# GPSClockISA.net
KiCad netlist of a schematic drawn in EAGLE
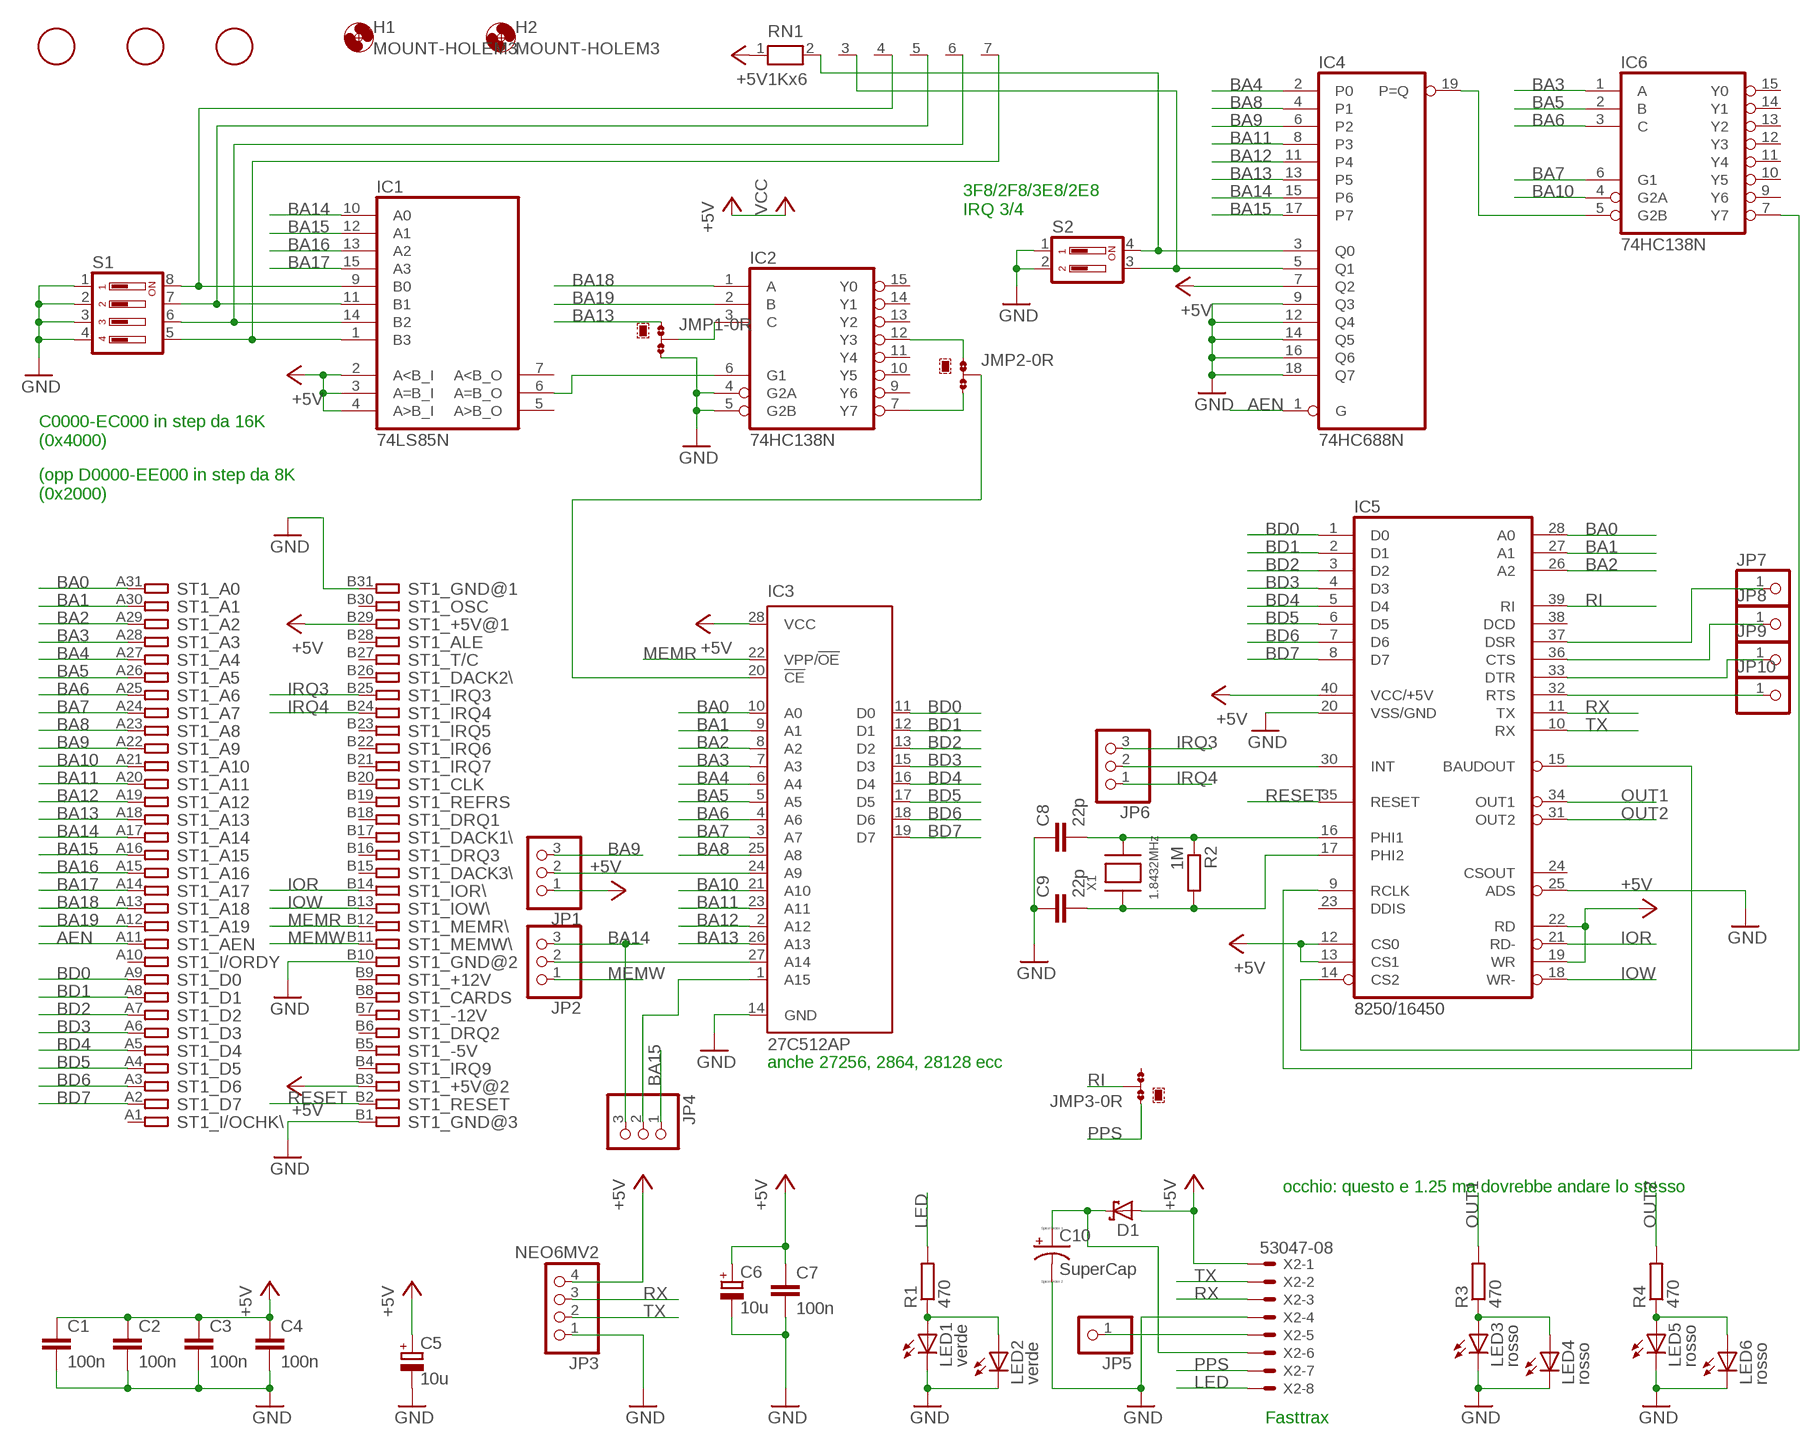
[diagram p0: schematic, sheet 1]

(export (version "E")
  (design (tool "Eeschema 10.0.6"))
  (components
    (comp (ref "C1")
      (value "100n")
      (footprint "eagle-import:C0805")
      (libsource (lib "eagle-import") (part "C-EUC0805"))
    )
    (comp (ref "C2")
      (value "100n")
      (footprint "eagle-import:C0805")
      (libsource (lib "eagle-import") (part "C-EUC0805"))
    )
    (comp (ref "C3")
      (value "100n")
      (footprint "eagle-import:C0805")
      (libsource (lib "eagle-import") (part "C-EUC0805"))
    )
    (comp (ref "C4")
      (value "100n")
      (footprint "eagle-import:C0805")
      (libsource (lib "eagle-import") (part "C-EUC0805"))
    )
    (comp (ref "C5")
      (value "10u")
      (footprint "eagle-import:SMC_D")
      (libsource (lib "eagle-import") (part "CPOL-EUSMCD"))
    )
    (comp (ref "C6")
      (value "10u")
      (footprint "eagle-import:SMC_C")
      (libsource (lib "eagle-import") (part "CPOL-EUSMCC"))
    )
    (comp (ref "C7")
      (value "100n")
      (footprint "eagle-import:C0805")
      (libsource (lib "eagle-import") (part "C-EUC0805"))
    )
    (comp (ref "C8")
      (value "22p")
      (footprint "eagle-import:C0805")
      (libsource (lib "eagle-import") (part "C-EUC0805"))
    )
    (comp (ref "C9")
      (value "22p")
      (footprint "eagle-import:C0805")
      (libsource (lib "eagle-import") (part "C-EUC0805"))
    )
    (comp (ref "C10")
      (value "SuperCap")
      (footprint "eagle-import:EB22,5D")
      (libsource (lib "eagle-import") (part "CPOL-USE10-22.5"))
    )
    (comp (ref "D1")
      (value "SCHOTTKY-DIODESMC")
      (footprint "eagle-import:SMC")
      (libsource (lib "eagle-import") (part "SCHOTTKY-DIODESMC"))
    )
    (comp (ref "F1")
      (value "FIDUCIAL")
      (footprint "eagle-import:FIDUCIAL_1MM")
      (libsource (lib "eagle-import") (part "FIDUCIAL"))
    )
    (comp (ref "F2")
      (value "FIDUCIAL")
      (footprint "eagle-import:FIDUCIAL_1MM")
      (libsource (lib "eagle-import") (part "FIDUCIAL"))
    )
    (comp (ref "F3")
      (value "FIDUCIAL")
      (footprint "eagle-import:FIDUCIAL_1MM")
      (libsource (lib "eagle-import") (part "FIDUCIAL"))
    )
    (comp (ref "H1")
      (value "MOUNT-HOLEM3")
      (footprint "eagle-import:M3")
      (libsource (lib "eagle-import") (part "MOUNT-HOLEM3"))
    )
    (comp (ref "H2")
      (value "MOUNT-HOLEM3")
      (footprint "eagle-import:M3")
      (libsource (lib "eagle-import") (part "MOUNT-HOLEM3"))
    )
    (comp (ref "IC1")
      (value "74LS85N")
      (footprint "eagle-import:DIL16")
      (libsource (lib "eagle-import") (part "7485NLS"))
    )
    (comp (ref "IC2")
      (value "74HC138N")
      (footprint "eagle-import:DIL16")
      (libsource (lib "eagle-import") (part "74138NHC"))
    )
    (comp (ref "IC3")
      (value "27C512AP")
      (footprint "eagle-import:DIL28-6")
      (fields (field (name "MPN") "M27C512-90B6"))
      (libsource (lib "eagle-import") (part "27512APC"))
    )
    (comp (ref "IC4")
      (value "74HC688N")
      (footprint "eagle-import:DIL20")
      (libsource (lib "eagle-import") (part "74688NHC"))
    )
    (comp (ref "IC5")
      (value "8250/16450")
      (footprint "eagle-import:DIL40")
      (libsource (lib "eagle-import") (part "8250"))
    )
    (comp (ref "IC6")
      (value "74HC138N")
      (footprint "eagle-import:DIL16")
      (libsource (lib "eagle-import") (part "74138NHC"))
    )
    (comp (ref "JMP1")
      (value "0R-JUMPC")
      (footprint "eagle-import:C0R-JMP")
      (libsource (lib "eagle-import") (part "0R-JUMPC"))
    )
    (comp (ref "JMP2")
      (value "0R-JUMPC")
      (footprint "eagle-import:C0R-JMP")
      (libsource (lib "eagle-import") (part "0R-JUMPC"))
    )
    (comp (ref "JMP3")
      (value "0R-JUMPC")
      (footprint "eagle-import:C0R-JMP")
      (libsource (lib "eagle-import") (part "0R-JUMPC"))
    )
    (comp (ref "JP1")
      (value "PINHD-1X03_2.54")
      (footprint "eagle-import:1X03")
      (libsource (lib "eagle-import") (part "PINHD-1X03_2.54"))
    )
    (comp (ref "JP2")
      (value "PINHD-1X03_2.54")
      (footprint "eagle-import:1X03")
      (libsource (lib "eagle-import") (part "PINHD-1X03_2.54"))
    )
    (comp (ref "JP3")
      (value "NEO6MV2")
      (footprint "eagle-import:1X04")
      (libsource (lib "eagle-import") (part "PINHD-1X4"))
    )
    (comp (ref "JP4")
      (value "PINHD-1X03_2.54")
      (footprint "eagle-import:1X03")
      (libsource (lib "eagle-import") (part "PINHD-1X03_2.54"))
    )
    (comp (ref "JP5")
      (value "PINHD-1X1")
      (footprint "eagle-import:1X01")
      (libsource (lib "eagle-import") (part "PINHD-1X1"))
    )
    (comp (ref "JP6")
      (value "PINHD-1X03_2.54")
      (footprint "eagle-import:1X03")
      (libsource (lib "eagle-import") (part "PINHD-1X03_2.54"))
    )
    (comp (ref "JP7")
      (value "PINHD-1X1")
      (footprint "eagle-import:1X01")
      (libsource (lib "eagle-import") (part "PINHD-1X1"))
    )
    (comp (ref "JP8")
      (value "PINHD-1X1")
      (footprint "eagle-import:1X01")
      (libsource (lib "eagle-import") (part "PINHD-1X1"))
    )
    (comp (ref "JP9")
      (value "PINHD-1X1")
      (footprint "eagle-import:1X01")
      (libsource (lib "eagle-import") (part "PINHD-1X1"))
    )
    (comp (ref "JP10")
      (value "PINHD-1X1")
      (footprint "eagle-import:1X01")
      (libsource (lib "eagle-import") (part "PINHD-1X1"))
    )
    (comp (ref "LED1")
      (value "verde")
      (footprint "eagle-import:CHIPLED_0805")
      (libsource (lib "eagle-import") (part "led_LEDCHIPLED_0805"))
    )
    (comp (ref "LED2")
      (value "verde")
      (footprint "eagle-import:LED3MM")
      (libsource (lib "eagle-import") (part "LED3MM"))
    )
    (comp (ref "LED3")
      (value "rosso")
      (footprint "eagle-import:CHIPLED_0805")
      (libsource (lib "eagle-import") (part "led_LEDCHIPLED_0805"))
    )
    (comp (ref "LED4")
      (value "rosso")
      (footprint "eagle-import:LED3MM")
      (libsource (lib "eagle-import") (part "LED3MM"))
    )
    (comp (ref "LED5")
      (value "rosso")
      (footprint "eagle-import:CHIPLED_0805")
      (libsource (lib "eagle-import") (part "led_LEDCHIPLED_0805"))
    )
    (comp (ref "LED6")
      (value "rosso")
      (footprint "eagle-import:LED3MM")
      (libsource (lib "eagle-import") (part "LED3MM"))
    )
    (comp (ref "R1")
      (value "470")
      (footprint "eagle-import:R0805")
      (libsource (lib "eagle-import") (part "R-EU_R0805"))
    )
    (comp (ref "R2")
      (value "1M")
      (footprint "eagle-import:R0805")
      (libsource (lib "eagle-import") (part "R-EU_R0805"))
    )
    (comp (ref "R3")
      (value "470")
      (footprint "eagle-import:R0805")
      (libsource (lib "eagle-import") (part "R-EU_R0805"))
    )
    (comp (ref "R4")
      (value "470")
      (footprint "eagle-import:R0805")
      (libsource (lib "eagle-import") (part "R-EU_R0805"))
    )
    (comp (ref "RN1")
      (value "1Kx6")
      (footprint "eagle-import:RN-7")
      (libsource (lib "eagle-import") (part "RN06"))
    )
    (comp (ref "S1")
      (value "DIP04YL")
      (footprint "eagle-import:DIP04YL")
      (libsource (lib "eagle-import") (part "DIP04YL"))
    )
    (comp (ref "S2")
      (value "DIP02YL")
      (footprint "eagle-import:DIP02YL")
      (libsource (lib "eagle-import") (part "DIP02YL"))
    )
    (comp (ref "ST1")
      (value "IBM8BIT")
      (footprint "eagle-import:IBM8BIT")
      (libsource (lib "eagle-import") (part "IBM8BIT"))
    )
    (comp (ref "X1")
      (value "1.8432MHz")
      (footprint "eagle-import:NX8045")
      (libsource (lib "eagle-import") (part "XTALNX8045"))
    )
    (comp (ref "X2")
      (value "53047-08")
      (footprint "eagle-import:53047-08")
      (fields (field (name "MPN") "53047-0810"))
      (libsource (lib "eagle-import") (part "53?-08047"))
    )
  )
  (nets
    (net (code "1") (name "+5V") (class "Default")
      (node (ref "C1") (pin "1") (pinfunction "1_1") (pintype "passive"))
      (node (ref "C2") (pin "1") (pinfunction "1_1") (pintype "passive"))
      (node (ref "C3") (pin "1") (pinfunction "1_1") (pintype "passive"))
      (node (ref "C4") (pin "1") (pinfunction "1_1") (pintype "passive"))
      (node (ref "C5") (pin "+") (pinfunction "+_+") (pintype "passive"))
      (node (ref "C6") (pin "+") (pinfunction "+_+") (pintype "passive"))
      (node (ref "C7") (pin "1") (pinfunction "1_1") (pintype "passive"))
      (node (ref "D1") (pin "A") (pinfunction "A_A") (pintype "passive"))
      (node (ref "IC1") (pin "2") (pinfunction "A<B_I_2") (pintype "input"))
      (node (ref "IC1") (pin "3") (pinfunction "A=B_I_3") (pintype "input"))
      (node (ref "IC1") (pin "4") (pinfunction "A>B_I_4") (pintype "input"))
      (node (ref "IC3") (pin "28") (pinfunction "VCC_28") (pintype "power_in"))
      (node (ref "IC4") (pin "7") (pinfunction "Q2_7") (pintype "input"))
      (node (ref "IC5") (pin "12") (pinfunction "CS0_12") (pintype "input"))
      (node (ref "IC5") (pin "13") (pinfunction "CS1_13") (pintype "input"))
      (node (ref "IC5") (pin "19") (pinfunction "WR_19") (pintype "input"))
      (node (ref "IC5") (pin "22") (pinfunction "RD_22") (pintype "input"))
      (node (ref "IC5") (pin "40") (pinfunction "VCC/+5V_40") (pintype "power_in"))
      (node (ref "JP1") (pin "1") (pinfunction "1_1") (pintype "passive"))
      (node (ref "JP3") (pin "4") (pinfunction "4_4") (pintype "passive"))
      (node (ref "RN1") (pin "1") (pinfunction "1_1") (pintype "passive"))
      (node (ref "ST1") (pin "B29") (pinfunction "P_B29") (pintype "bidirectional"))
      (node (ref "ST1") (pin "B3") (pinfunction "P_B3") (pintype "bidirectional"))
      (node (ref "X2") (pin "1") (pinfunction "S_1") (pintype "passive"))
    )
    (net (code "2") (name "/AEN") (class "Default")
      (node (ref "IC4") (pin "1") (pinfunction "G_1") (pintype "input"))
      (node (ref "ST1") (pin "A11") (pinfunction "P_A11") (pintype "bidirectional"))
    )
    (net (code "3") (name "/BA0") (class "Default")
      (node (ref "IC3") (pin "10") (pinfunction "A0_10") (pintype "input"))
      (node (ref "IC5") (pin "28") (pinfunction "A0_28") (pintype "input"))
      (node (ref "ST1") (pin "A31") (pinfunction "P_A31") (pintype "bidirectional"))
    )
    (net (code "4") (name "/BA1") (class "Default")
      (node (ref "IC3") (pin "9") (pinfunction "A1_9") (pintype "input"))
      (node (ref "IC5") (pin "27") (pinfunction "A1_27") (pintype "input"))
      (node (ref "ST1") (pin "A30") (pinfunction "P_A30") (pintype "bidirectional"))
    )
    (net (code "5") (name "/BA2") (class "Default")
      (node (ref "IC3") (pin "8") (pinfunction "A2_8") (pintype "input"))
      (node (ref "IC5") (pin "26") (pinfunction "A2_26") (pintype "input"))
      (node (ref "ST1") (pin "A29") (pinfunction "P_A29") (pintype "bidirectional"))
    )
    (net (code "6") (name "/BA3") (class "Default")
      (node (ref "IC3") (pin "7") (pinfunction "A3_7") (pintype "input"))
      (node (ref "IC6") (pin "1") (pinfunction "A_1") (pintype "input"))
      (node (ref "ST1") (pin "A28") (pinfunction "P_A28") (pintype "bidirectional"))
    )
    (net (code "7") (name "/BA4") (class "Default")
      (node (ref "IC3") (pin "6") (pinfunction "A4_6") (pintype "input"))
      (node (ref "IC4") (pin "2") (pinfunction "P0_2") (pintype "input"))
      (node (ref "ST1") (pin "A27") (pinfunction "P_A27") (pintype "bidirectional"))
    )
    (net (code "8") (name "/BA5") (class "Default")
      (node (ref "IC3") (pin "5") (pinfunction "A5_5") (pintype "input"))
      (node (ref "IC6") (pin "2") (pinfunction "B_2") (pintype "input"))
      (node (ref "ST1") (pin "A26") (pinfunction "P_A26") (pintype "bidirectional"))
    )
    (net (code "9") (name "/BA6") (class "Default")
      (node (ref "IC3") (pin "4") (pinfunction "A6_4") (pintype "input"))
      (node (ref "IC6") (pin "3") (pinfunction "C_3") (pintype "input"))
      (node (ref "ST1") (pin "A25") (pinfunction "P_A25") (pintype "bidirectional"))
    )
    (net (code "10") (name "/BA7") (class "Default")
      (node (ref "IC3") (pin "3") (pinfunction "A7_3") (pintype "input"))
      (node (ref "IC6") (pin "6") (pinfunction "G1_6") (pintype "input"))
      (node (ref "ST1") (pin "A24") (pinfunction "P_A24") (pintype "bidirectional"))
    )
    (net (code "11") (name "/BA8") (class "Default")
      (node (ref "IC3") (pin "25") (pinfunction "A8_25") (pintype "input"))
      (node (ref "IC4") (pin "4") (pinfunction "P1_4") (pintype "input"))
      (node (ref "ST1") (pin "A23") (pinfunction "P_A23") (pintype "bidirectional"))
    )
    (net (code "12") (name "/BA9") (class "Default")
      (node (ref "IC4") (pin "6") (pinfunction "P2_6") (pintype "input"))
      (node (ref "JP1") (pin "3") (pinfunction "3_3") (pintype "passive"))
      (node (ref "ST1") (pin "A22") (pinfunction "P_A22") (pintype "bidirectional"))
    )
    (net (code "13") (name "/BA10") (class "Default")
      (node (ref "IC3") (pin "21") (pinfunction "A10_21") (pintype "input"))
      (node (ref "IC6") (pin "4") (pinfunction "G2A_4") (pintype "input"))
      (node (ref "ST1") (pin "A21") (pinfunction "P_A21") (pintype "bidirectional"))
    )
    (net (code "14") (name "/BA11") (class "Default")
      (node (ref "IC3") (pin "23") (pinfunction "A11_23") (pintype "input"))
      (node (ref "IC4") (pin "8") (pinfunction "P3_8") (pintype "input"))
      (node (ref "ST1") (pin "A20") (pinfunction "P_A20") (pintype "bidirectional"))
    )
    (net (code "15") (name "/BA12") (class "Default")
      (node (ref "IC3") (pin "2") (pinfunction "A12_2") (pintype "input"))
      (node (ref "IC4") (pin "11") (pinfunction "P4_11") (pintype "input"))
      (node (ref "ST1") (pin "A19") (pinfunction "P_A19") (pintype "bidirectional"))
    )
    (net (code "16") (name "/BA13") (class "Default")
      (node (ref "IC3") (pin "26") (pinfunction "A13_26") (pintype "input"))
      (node (ref "IC4") (pin "13") (pinfunction "P5_13") (pintype "input"))
      (node (ref "JMP1") (pin "1") (pinfunction "1_1") (pintype "passive"))
      (node (ref "ST1") (pin "A18") (pinfunction "P_A18") (pintype "bidirectional"))
    )
    (net (code "17") (name "/BA14") (class "Default")
      (node (ref "IC1") (pin "10") (pinfunction "A0_10") (pintype "input"))
      (node (ref "IC4") (pin "15") (pinfunction "P6_15") (pintype "input"))
      (node (ref "JP2") (pin "3") (pinfunction "3_3") (pintype "passive"))
      (node (ref "JP4") (pin "3") (pinfunction "3_3") (pintype "passive"))
      (node (ref "ST1") (pin "A17") (pinfunction "P_A17") (pintype "bidirectional"))
    )
    (net (code "18") (name "/BA15") (class "Default")
      (node (ref "IC1") (pin "12") (pinfunction "A1_12") (pintype "input"))
      (node (ref "IC4") (pin "17") (pinfunction "P7_17") (pintype "input"))
      (node (ref "JP4") (pin "1") (pinfunction "1_1") (pintype "passive"))
      (node (ref "ST1") (pin "A16") (pinfunction "P_A16") (pintype "bidirectional"))
    )
    (net (code "19") (name "/BA16") (class "Default")
      (node (ref "IC1") (pin "13") (pinfunction "A2_13") (pintype "input"))
      (node (ref "ST1") (pin "A15") (pinfunction "P_A15") (pintype "bidirectional"))
    )
    (net (code "20") (name "/BA17") (class "Default")
      (node (ref "IC1") (pin "15") (pinfunction "A3_15") (pintype "input"))
      (node (ref "ST1") (pin "A14") (pinfunction "P_A14") (pintype "bidirectional"))
    )
    (net (code "21") (name "/BA18") (class "Default")
      (node (ref "IC2") (pin "1") (pinfunction "A_1") (pintype "input"))
      (node (ref "ST1") (pin "A13") (pinfunction "P_A13") (pintype "bidirectional"))
    )
    (net (code "22") (name "/BA19") (class "Default")
      (node (ref "IC2") (pin "2") (pinfunction "B_2") (pintype "input"))
      (node (ref "ST1") (pin "A12") (pinfunction "P_A12") (pintype "bidirectional"))
    )
    (net (code "23") (name "/BD0") (class "Default")
      (node (ref "IC3") (pin "11") (pinfunction "D0_11") (pintype "tri_state"))
      (node (ref "IC5") (pin "1") (pinfunction "D0_1") (pintype "bidirectional"))
      (node (ref "ST1") (pin "A9") (pinfunction "P_A9") (pintype "bidirectional"))
    )
    (net (code "24") (name "/BD1") (class "Default")
      (node (ref "IC3") (pin "12") (pinfunction "D1_12") (pintype "tri_state"))
      (node (ref "IC5") (pin "2") (pinfunction "D1_2") (pintype "bidirectional"))
      (node (ref "ST1") (pin "A8") (pinfunction "P_A8") (pintype "bidirectional"))
    )
    (net (code "25") (name "/BD2") (class "Default")
      (node (ref "IC3") (pin "13") (pinfunction "D2_13") (pintype "tri_state"))
      (node (ref "IC5") (pin "3") (pinfunction "D2_3") (pintype "bidirectional"))
      (node (ref "ST1") (pin "A7") (pinfunction "P_A7") (pintype "bidirectional"))
    )
    (net (code "26") (name "/BD3") (class "Default")
      (node (ref "IC3") (pin "15") (pinfunction "D3_15") (pintype "tri_state"))
      (node (ref "IC5") (pin "4") (pinfunction "D3_4") (pintype "bidirectional"))
      (node (ref "ST1") (pin "A6") (pinfunction "P_A6") (pintype "bidirectional"))
    )
    (net (code "27") (name "/BD4") (class "Default")
      (node (ref "IC3") (pin "16") (pinfunction "D4_16") (pintype "tri_state"))
      (node (ref "IC5") (pin "5") (pinfunction "D4_5") (pintype "bidirectional"))
      (node (ref "ST1") (pin "A5") (pinfunction "P_A5") (pintype "bidirectional"))
    )
    (net (code "28") (name "/BD5") (class "Default")
      (node (ref "IC3") (pin "17") (pinfunction "D5_17") (pintype "tri_state"))
      (node (ref "IC5") (pin "6") (pinfunction "D5_6") (pintype "bidirectional"))
      (node (ref "ST1") (pin "A4") (pinfunction "P_A4") (pintype "bidirectional"))
    )
    (net (code "29") (name "/BD6") (class "Default")
      (node (ref "IC3") (pin "18") (pinfunction "D6_18") (pintype "tri_state"))
      (node (ref "IC5") (pin "7") (pinfunction "D6_7") (pintype "bidirectional"))
      (node (ref "ST1") (pin "A3") (pinfunction "P_A3") (pintype "bidirectional"))
    )
    (net (code "30") (name "/BD7") (class "Default")
      (node (ref "IC3") (pin "19") (pinfunction "D7_19") (pintype "tri_state"))
      (node (ref "IC5") (pin "8") (pinfunction "D7_8") (pintype "bidirectional"))
      (node (ref "ST1") (pin "A2") (pinfunction "P_A2") (pintype "bidirectional"))
    )
    (net (code "31") (name "/IOR") (class "Default")
      (node (ref "IC5") (pin "21") (pinfunction "RD-_21") (pintype "input"))
      (node (ref "ST1") (pin "B14") (pinfunction "P_B14") (pintype "bidirectional"))
    )
    (net (code "32") (name "/IOW") (class "Default")
      (node (ref "IC5") (pin "18") (pinfunction "WR-_18") (pintype "input"))
      (node (ref "ST1") (pin "B13") (pinfunction "P_B13") (pintype "bidirectional"))
    )
    (net (code "33") (name "/IRQ3") (class "Default")
      (node (ref "JP6") (pin "3") (pinfunction "3_3") (pintype "passive"))
      (node (ref "ST1") (pin "B25") (pinfunction "P_B25") (pintype "bidirectional"))
    )
    (net (code "34") (name "/IRQ4") (class "Default")
      (node (ref "JP6") (pin "1") (pinfunction "1_1") (pintype "passive"))
      (node (ref "ST1") (pin "B24") (pinfunction "P_B24") (pintype "bidirectional"))
    )
    (net (code "35") (name "/LED") (class "Default")
      (node (ref "R1") (pin "2") (pinfunction "2_2") (pintype "passive"))
      (node (ref "X2") (pin "8") (pinfunction "S_8") (pintype "passive"))
    )
    (net (code "36") (name "/MEMR") (class "Default")
      (node (ref "IC3") (pin "22") (pinfunction "VPP/~{OE}_22") (pintype "input"))
      (node (ref "ST1") (pin "B12") (pinfunction "P_B12") (pintype "bidirectional"))
    )
    (net (code "37") (name "/MEMW") (class "Default")
      (node (ref "JP2") (pin "1") (pinfunction "1_1") (pintype "passive"))
      (node (ref "ST1") (pin "B11") (pinfunction "P_B11") (pintype "bidirectional"))
    )
    (net (code "38") (name "/OUT1") (class "Default")
      (node (ref "IC5") (pin "34") (pinfunction "OUT1_34") (pintype "input"))
      (node (ref "R3") (pin "2") (pinfunction "2_2") (pintype "passive"))
    )
    (net (code "39") (name "/OUT2") (class "Default")
      (node (ref "IC5") (pin "31") (pinfunction "OUT2_31") (pintype "input"))
      (node (ref "R4") (pin "2") (pinfunction "2_2") (pintype "passive"))
    )
    (net (code "40") (name "/PPS") (class "Default")
      (node (ref "JMP3") (pin "1") (pinfunction "1_1") (pintype "passive"))
      (node (ref "X2") (pin "7") (pinfunction "S_7") (pintype "passive"))
    )
    (net (code "41") (name "/RESET") (class "Default")
      (node (ref "IC5") (pin "35") (pinfunction "RESET_35") (pintype "input"))
      (node (ref "ST1") (pin "B2") (pinfunction "P_B2") (pintype "bidirectional"))
    )
    (net (code "42") (name "/RI") (class "Default")
      (node (ref "IC5") (pin "39") (pinfunction "RI_39") (pintype "output"))
      (node (ref "JMP3") (pin "2") (pinfunction "2_2") (pintype "passive"))
    )
    (net (code "43") (name "/RX") (class "Default")
      (node (ref "IC5") (pin "11") (pinfunction "TX_11") (pintype "output"))
      (node (ref "JP3") (pin "3") (pinfunction "3_3") (pintype "passive"))
      (node (ref "X2") (pin "3") (pinfunction "S_3") (pintype "passive"))
    )
    (net (code "44") (name "/TX") (class "Default")
      (node (ref "IC5") (pin "10") (pinfunction "RX_10") (pintype "input"))
      (node (ref "JP3") (pin "2") (pinfunction "2_2") (pintype "passive"))
      (node (ref "X2") (pin "2") (pinfunction "S_2") (pintype "passive"))
    )
    (net (code "45") (name "GND") (class "Default")
      (node (ref "C1") (pin "2") (pinfunction "2_2") (pintype "passive"))
      (node (ref "C10") (pin "-") (pinfunction "-_-") (pintype "passive"))
      (node (ref "C2") (pin "2") (pinfunction "2_2") (pintype "passive"))
      (node (ref "C3") (pin "2") (pinfunction "2_2") (pintype "passive"))
      (node (ref "C4") (pin "2") (pinfunction "2_2") (pintype "passive"))
      (node (ref "C5") (pin "-") (pinfunction "-_-") (pintype "passive"))
      (node (ref "C6") (pin "-") (pinfunction "-_-") (pintype "passive"))
      (node (ref "C7") (pin "2") (pinfunction "2_2") (pintype "passive"))
      (node (ref "C8") (pin "1") (pinfunction "1_1") (pintype "passive"))
      (node (ref "C9") (pin "1") (pinfunction "1_1") (pintype "passive"))
      (node (ref "IC2") (pin "4") (pinfunction "G2A_4") (pintype "input"))
      (node (ref "IC2") (pin "5") (pinfunction "G2B_5") (pintype "input"))
      (node (ref "IC3") (pin "14") (pinfunction "GND_14") (pintype "power_in"))
      (node (ref "IC4") (pin "12") (pinfunction "Q4_12") (pintype "input"))
      (node (ref "IC4") (pin "14") (pinfunction "Q5_14") (pintype "input"))
      (node (ref "IC4") (pin "16") (pinfunction "Q6_16") (pintype "input"))
      (node (ref "IC4") (pin "18") (pinfunction "Q7_18") (pintype "input"))
      (node (ref "IC4") (pin "9") (pinfunction "Q3_9") (pintype "input"))
      (node (ref "IC5") (pin "20") (pinfunction "VSS/GND_20") (pintype "power_in"))
      (node (ref "IC5") (pin "25") (pinfunction "ADS_25") (pintype "input"))
      (node (ref "JMP1") (pin "3") (pinfunction "3_3") (pintype "passive"))
      (node (ref "JP3") (pin "1") (pinfunction "1_1") (pintype "passive"))
      (node (ref "LED1") (pin "C") (pinfunction "C_C") (pintype "passive"))
      (node (ref "LED2") (pin "K") (pinfunction "C_K") (pintype "passive"))
      (node (ref "LED3") (pin "C") (pinfunction "C_C") (pintype "passive"))
      (node (ref "LED4") (pin "K") (pinfunction "C_K") (pintype "passive"))
      (node (ref "LED5") (pin "C") (pinfunction "C_C") (pintype "passive"))
      (node (ref "LED6") (pin "K") (pinfunction "C_K") (pintype "passive"))
      (node (ref "S1") (pin "1") (pinfunction "1_1") (pintype "passive"))
      (node (ref "S1") (pin "2") (pinfunction "2_2") (pintype "passive"))
      (node (ref "S1") (pin "3") (pinfunction "3_3") (pintype "passive"))
      (node (ref "S1") (pin "4") (pinfunction "4_4") (pintype "passive"))
      (node (ref "S2") (pin "1") (pinfunction "1_1") (pintype "passive"))
      (node (ref "S2") (pin "2") (pinfunction "2_2") (pintype "passive"))
      (node (ref "ST1") (pin "B1") (pinfunction "P_B1") (pintype "bidirectional"))
      (node (ref "ST1") (pin "B10") (pinfunction "P_B10") (pintype "bidirectional"))
      (node (ref "ST1") (pin "B31") (pinfunction "P_B31") (pintype "bidirectional"))
      (node (ref "X2") (pin "4") (pinfunction "S_4") (pintype "passive"))
    )
    (net (code "46") (name "Net-(IC1A-A=B_O)") (class "Default")
      (node (ref "IC1") (pin "6") (pinfunction "A=B_O_6") (pintype "output"))
      (node (ref "IC2") (pin "6") (pinfunction "G1_6") (pintype "input"))
    )
    (net (code "47") (name "Net-(IC1A-B0)") (class "Default")
      (node (ref "IC1") (pin "9") (pinfunction "B0_9") (pintype "input"))
      (node (ref "RN1") (pin "4") (pinfunction "4_4") (pintype "passive"))
      (node (ref "S1") (pin "8") (pinfunction "8_8") (pintype "passive"))
    )
    (net (code "48") (name "Net-(IC1A-B1)") (class "Default")
      (node (ref "IC1") (pin "11") (pinfunction "B1_11") (pintype "input"))
      (node (ref "RN1") (pin "5") (pinfunction "5_5") (pintype "passive"))
      (node (ref "S1") (pin "7") (pinfunction "7_7") (pintype "passive"))
    )
    (net (code "49") (name "Net-(IC1A-B2)") (class "Default")
      (node (ref "IC1") (pin "14") (pinfunction "B2_14") (pintype "input"))
      (node (ref "RN1") (pin "6") (pinfunction "6_6") (pintype "passive"))
      (node (ref "S1") (pin "6") (pinfunction "6_6") (pintype "passive"))
    )
    (net (code "50") (name "Net-(IC1A-B3)") (class "Default")
      (node (ref "IC1") (pin "1") (pinfunction "B3_1") (pintype "input"))
      (node (ref "RN1") (pin "7") (pinfunction "7_7") (pintype "passive"))
      (node (ref "S1") (pin "5") (pinfunction "5_5") (pintype "passive"))
    )
    (net (code "51") (name "Net-(IC2A-C)") (class "Default")
      (node (ref "IC2") (pin "3") (pinfunction "C_3") (pintype "input"))
      (node (ref "JMP1") (pin "2") (pinfunction "2_2") (pintype "passive"))
    )
    (net (code "52") (name "Net-(IC2A-Y3)") (class "Default")
      (node (ref "IC2") (pin "12") (pinfunction "Y3_12") (pintype "output"))
      (node (ref "JMP2") (pin "1") (pinfunction "1_1") (pintype "passive"))
    )
    (net (code "53") (name "Net-(IC2A-Y7)") (class "Default")
      (node (ref "IC2") (pin "7") (pinfunction "Y7_7") (pintype "output"))
      (node (ref "JMP2") (pin "3") (pinfunction "3_3") (pintype "passive"))
    )
    (net (code "54") (name "Net-(IC3-A9)") (class "Default")
      (node (ref "IC3") (pin "24") (pinfunction "A9_24") (pintype "input"))
      (node (ref "JP1") (pin "2") (pinfunction "2_2") (pintype "passive"))
    )
    (net (code "55") (name "Net-(IC3-A14)") (class "Default")
      (node (ref "IC3") (pin "27") (pinfunction "A14_27") (pintype "input"))
      (node (ref "JP2") (pin "2") (pinfunction "2_2") (pintype "passive"))
    )
    (net (code "56") (name "Net-(IC3-A15)") (class "Default")
      (node (ref "IC3") (pin "1") (pinfunction "A15_1") (pintype "input"))
      (node (ref "JP4") (pin "2") (pinfunction "2_2") (pintype "passive"))
    )
    (net (code "57") (name "Net-(IC3-~{CE})") (class "Default")
      (node (ref "IC3") (pin "20") (pinfunction "~{CE}_20") (pintype "input"))
      (node (ref "JMP2") (pin "2") (pinfunction "2_2") (pintype "passive"))
    )
    (net (code "58") (name "Net-(IC4A-P=Q)") (class "Default")
      (node (ref "IC4") (pin "19") (pinfunction "P=Q_19") (pintype "output"))
      (node (ref "IC6") (pin "5") (pinfunction "G2B_5") (pintype "input"))
    )
    (net (code "59") (name "Net-(IC4A-Q0)") (class "Default")
      (node (ref "IC4") (pin "3") (pinfunction "Q0_3") (pintype "input"))
      (node (ref "RN1") (pin "2") (pinfunction "2_2") (pintype "passive"))
      (node (ref "S2") (pin "4") (pinfunction "4_4") (pintype "passive"))
    )
    (net (code "60") (name "Net-(IC4A-Q1)") (class "Default")
      (node (ref "IC4") (pin "5") (pinfunction "Q1_5") (pintype "input"))
      (node (ref "RN1") (pin "3") (pinfunction "3_3") (pintype "passive"))
      (node (ref "S2") (pin "3") (pinfunction "3_3") (pintype "passive"))
    )
    (net (code "61") (name "Net-(IC5-BAUDOUT)") (class "Default")
      (node (ref "IC5") (pin "15") (pinfunction "BAUDOUT_15") (pintype "output"))
      (node (ref "IC5") (pin "9") (pinfunction "RCLK_9") (pintype "input"))
    )
    (net (code "62") (name "Net-(IC5-CS2)") (class "Default")
      (node (ref "IC5") (pin "14") (pinfunction "CS2_14") (pintype "input"))
      (node (ref "IC6") (pin "7") (pinfunction "Y7_7") (pintype "output"))
    )
    (net (code "63") (name "Net-(IC5-CTS)") (class "Default")
      (node (ref "IC5") (pin "36") (pinfunction "CTS_36") (pintype "output"))
      (node (ref "JP8") (pin "1") (pinfunction "1_1") (pintype "passive"))
    )
    (net (code "64") (name "Net-(IC5-DSR)") (class "Default")
      (node (ref "IC5") (pin "37") (pinfunction "DSR_37") (pintype "output"))
      (node (ref "JP7") (pin "1") (pinfunction "1_1") (pintype "passive"))
    )
    (net (code "65") (name "Net-(IC5-DTR)") (class "Default")
      (node (ref "IC5") (pin "33") (pinfunction "DTR_33") (pintype "output"))
      (node (ref "JP9") (pin "1") (pinfunction "1_1") (pintype "passive"))
    )
    (net (code "66") (name "Net-(IC5-INT)") (class "Default")
      (node (ref "IC5") (pin "30") (pinfunction "INT_30") (pintype "output"))
      (node (ref "JP6") (pin "2") (pinfunction "2_2") (pintype "passive"))
    )
    (net (code "67") (name "Net-(IC5-PHI1)") (class "Default")
      (node (ref "C8") (pin "2") (pinfunction "2_2") (pintype "passive"))
      (node (ref "IC5") (pin "16") (pinfunction "PHI1_16") (pintype "input"))
      (node (ref "R2") (pin "1") (pinfunction "1_1") (pintype "passive"))
      (node (ref "X1") (pin "P$2") (pinfunction "P$2_P$2") (pintype "bidirectional"))
    )
    (net (code "68") (name "Net-(IC5-PHI2)") (class "Default")
      (node (ref "C9") (pin "2") (pinfunction "2_2") (pintype "passive"))
      (node (ref "IC5") (pin "17") (pinfunction "PHI2_17") (pintype "input"))
      (node (ref "R2") (pin "2") (pinfunction "2_2") (pintype "passive"))
      (node (ref "X1") (pin "P$1") (pinfunction "P$1_P$1") (pintype "bidirectional"))
    )
    (net (code "69") (name "Net-(IC5-RTS)") (class "Default")
      (node (ref "IC5") (pin "32") (pinfunction "RTS_32") (pintype "output"))
      (node (ref "JP10") (pin "1") (pinfunction "1_1") (pintype "passive"))
    )
    (net (code "70") (name "Net-(LED1-PadA)") (class "Default")
      (node (ref "LED1") (pin "A") (pinfunction "A_A") (pintype "passive"))
      (node (ref "LED2") (pin "A") (pinfunction "A_A") (pintype "passive"))
      (node (ref "R1") (pin "1") (pinfunction "1_1") (pintype "passive"))
    )
    (net (code "71") (name "Net-(LED3-PadA)") (class "Default")
      (node (ref "LED3") (pin "A") (pinfunction "A_A") (pintype "passive"))
      (node (ref "LED4") (pin "A") (pinfunction "A_A") (pintype "passive"))
      (node (ref "R3") (pin "1") (pinfunction "1_1") (pintype "passive"))
    )
    (net (code "72") (name "Net-(LED5-PadA)") (class "Default")
      (node (ref "LED5") (pin "A") (pinfunction "A_A") (pintype "passive"))
      (node (ref "LED6") (pin "A") (pinfunction "A_A") (pintype "passive"))
      (node (ref "R4") (pin "1") (pinfunction "1_1") (pintype "passive"))
    )
    (net (code "73") (name "Net-(X2E-S)") (class "Default")
      (node (ref "JP5") (pin "1") (pinfunction "1_1") (pintype "passive"))
      (node (ref "X2") (pin "5") (pinfunction "S_5") (pintype "passive"))
    )
    (net (code "74") (name "Net-(X2F-S)") (class "Default")
      (node (ref "C10") (pin "+") (pinfunction "+_+") (pintype "passive"))
      (node (ref "D1") (pin "C") (pinfunction "C_C") (pintype "passive"))
      (node (ref "X2") (pin "6") (pinfunction "S_6") (pintype "passive"))
    )
    (net (code "75") (name "unconnected-(IC1A-A<B_O-Pad7)") (class "Default")
      (node (ref "IC1") (pin "7") (pinfunction "A<B_O_7") (pintype "output"))
    )
    (net (code "76") (name "unconnected-(IC1A-A>B_O-Pad5)") (class "Default")
      (node (ref "IC1") (pin "5") (pinfunction "A>B_O_5") (pintype "output"))
    )
    (net (code "77") (name "unconnected-(IC2A-Y0-Pad15)") (class "Default")
      (node (ref "IC2") (pin "15") (pinfunction "Y0_15") (pintype "output"))
    )
    (net (code "78") (name "unconnected-(IC2A-Y1-Pad14)") (class "Default")
      (node (ref "IC2") (pin "14") (pinfunction "Y1_14") (pintype "output"))
    )
    (net (code "79") (name "unconnected-(IC2A-Y2-Pad13)") (class "Default")
      (node (ref "IC2") (pin "13") (pinfunction "Y2_13") (pintype "output"))
    )
    (net (code "80") (name "unconnected-(IC2A-Y4-Pad11)") (class "Default")
      (node (ref "IC2") (pin "11") (pinfunction "Y4_11") (pintype "output"))
    )
    (net (code "81") (name "unconnected-(IC2A-Y5-Pad10)") (class "Default")
      (node (ref "IC2") (pin "10") (pinfunction "Y5_10") (pintype "output"))
    )
    (net (code "82") (name "unconnected-(IC2A-Y6-Pad9)") (class "Default")
      (node (ref "IC2") (pin "9") (pinfunction "Y6_9") (pintype "output"))
    )
    (net (code "83") (name "unconnected-(IC5-CSOUT-Pad24)") (class "Default")
      (node (ref "IC5") (pin "24") (pinfunction "CSOUT_24") (pintype "output"))
    )
    (net (code "84") (name "unconnected-(IC5-DCD-Pad38)") (class "Default")
      (node (ref "IC5") (pin "38") (pinfunction "DCD_38") (pintype "output"))
    )
    (net (code "85") (name "unconnected-(IC5-DDIS-Pad23)") (class "Default")
      (node (ref "IC5") (pin "23") (pinfunction "DDIS_23") (pintype "output"))
    )
    (net (code "86") (name "unconnected-(IC6A-Y0-Pad15)") (class "Default")
      (node (ref "IC6") (pin "15") (pinfunction "Y0_15") (pintype "output"))
    )
    (net (code "87") (name "unconnected-(IC6A-Y1-Pad14)") (class "Default")
      (node (ref "IC6") (pin "14") (pinfunction "Y1_14") (pintype "output"))
    )
    (net (code "88") (name "unconnected-(IC6A-Y2-Pad13)") (class "Default")
      (node (ref "IC6") (pin "13") (pinfunction "Y2_13") (pintype "output"))
    )
    (net (code "89") (name "unconnected-(IC6A-Y3-Pad12)") (class "Default")
      (node (ref "IC6") (pin "12") (pinfunction "Y3_12") (pintype "output"))
    )
    (net (code "90") (name "unconnected-(IC6A-Y4-Pad11)") (class "Default")
      (node (ref "IC6") (pin "11") (pinfunction "Y4_11") (pintype "output"))
    )
    (net (code "91") (name "unconnected-(IC6A-Y5-Pad10)") (class "Default")
      (node (ref "IC6") (pin "10") (pinfunction "Y5_10") (pintype "output"))
    )
    (net (code "92") (name "unconnected-(IC6A-Y6-Pad9)") (class "Default")
      (node (ref "IC6") (pin "9") (pinfunction "Y6_9") (pintype "output"))
    )
    (net (code "93") (name "unconnected-(JMP3-Pad3)") (class "Default")
      (node (ref "JMP3") (pin "3") (pinfunction "3_3") (pintype "passive"))
    )
    (net (code "94") (name "unconnected-(ST1A-P-PadB9)") (class "Default")
      (node (ref "ST1") (pin "B9") (pinfunction "P_B9") (pintype "bidirectional"))
    )
    (net (code "95") (name "unconnected-(ST1AA-P-PadB28)") (class "Default")
      (node (ref "ST1") (pin "B28") (pinfunction "P_B28") (pintype "bidirectional"))
    )
    (net (code "96") (name "unconnected-(ST1AB-P-PadB8)") (class "Default")
      (node (ref "ST1") (pin "B8") (pinfunction "P_B8") (pintype "bidirectional"))
    )
    (net (code "97") (name "unconnected-(ST1AC-P-PadB20)") (class "Default")
      (node (ref "ST1") (pin "B20") (pinfunction "P_B20") (pintype "bidirectional"))
    )
    (net (code "98") (name "unconnected-(ST1AL-P-PadB17)") (class "Default")
      (node (ref "ST1") (pin "B17") (pinfunction "P_B17") (pintype "bidirectional"))
    )
    (net (code "99") (name "unconnected-(ST1AM-P-PadB26)") (class "Default")
      (node (ref "ST1") (pin "B26") (pinfunction "P_B26") (pintype "bidirectional"))
    )
    (net (code "100") (name "unconnected-(ST1AN-P-PadB15)") (class "Default")
      (node (ref "ST1") (pin "B15") (pinfunction "P_B15") (pintype "bidirectional"))
    )
    (net (code "101") (name "unconnected-(ST1AO-P-PadB18)") (class "Default")
      (node (ref "ST1") (pin "B18") (pinfunction "P_B18") (pintype "bidirectional"))
    )
    (net (code "102") (name "unconnected-(ST1AP-P-PadB6)") (class "Default")
      (node (ref "ST1") (pin "B6") (pinfunction "P_B6") (pintype "bidirectional"))
    )
    (net (code "103") (name "unconnected-(ST1AQ-P-PadB16)") (class "Default")
      (node (ref "ST1") (pin "B16") (pinfunction "P_B16") (pintype "bidirectional"))
    )
    (net (code "104") (name "unconnected-(ST1AU-P-PadA1)") (class "Default")
      (node (ref "ST1") (pin "A1") (pinfunction "P_A1") (pintype "bidirectional"))
    )
    (net (code "105") (name "unconnected-(ST1AV-P-PadA10)") (class "Default")
      (node (ref "ST1") (pin "A10") (pinfunction "P_A10") (pintype "bidirectional"))
    )
    (net (code "106") (name "unconnected-(ST1BA-P-PadB23)") (class "Default")
      (node (ref "ST1") (pin "B23") (pinfunction "P_B23") (pintype "bidirectional"))
    )
    (net (code "107") (name "unconnected-(ST1BB-P-PadB22)") (class "Default")
      (node (ref "ST1") (pin "B22") (pinfunction "P_B22") (pintype "bidirectional"))
    )
    (net (code "108") (name "unconnected-(ST1BC-P-PadB21)") (class "Default")
      (node (ref "ST1") (pin "B21") (pinfunction "P_B21") (pintype "bidirectional"))
    )
    (net (code "109") (name "unconnected-(ST1BD-P-PadB4)") (class "Default")
      (node (ref "ST1") (pin "B4") (pinfunction "P_B4") (pintype "bidirectional"))
    )
    (net (code "110") (name "unconnected-(ST1BG-P-PadB30)") (class "Default")
      (node (ref "ST1") (pin "B30") (pinfunction "P_B30") (pintype "bidirectional"))
    )
    (net (code "111") (name "unconnected-(ST1BH-P-PadB19)") (class "Default")
      (node (ref "ST1") (pin "B19") (pinfunction "P_B19") (pintype "bidirectional"))
    )
    (net (code "112") (name "unconnected-(ST1BJ-P-PadB27)") (class "Default")
      (node (ref "ST1") (pin "B27") (pinfunction "P_B27") (pintype "bidirectional"))
    )
    (net (code "113") (name "unconnected-(ST1D-P-PadB7)") (class "Default")
      (node (ref "ST1") (pin "B7") (pinfunction "P_B7") (pintype "bidirectional"))
    )
    (net (code "114") (name "unconnected-(ST1E-P-PadB5)") (class "Default")
      (node (ref "ST1") (pin "B5") (pinfunction "P_B5") (pintype "bidirectional"))
    )
  )
)
